# SCH_NFC-card-Michael_2024-10-10.net
KiCad netlist of a schematic drawn in EasyEDA
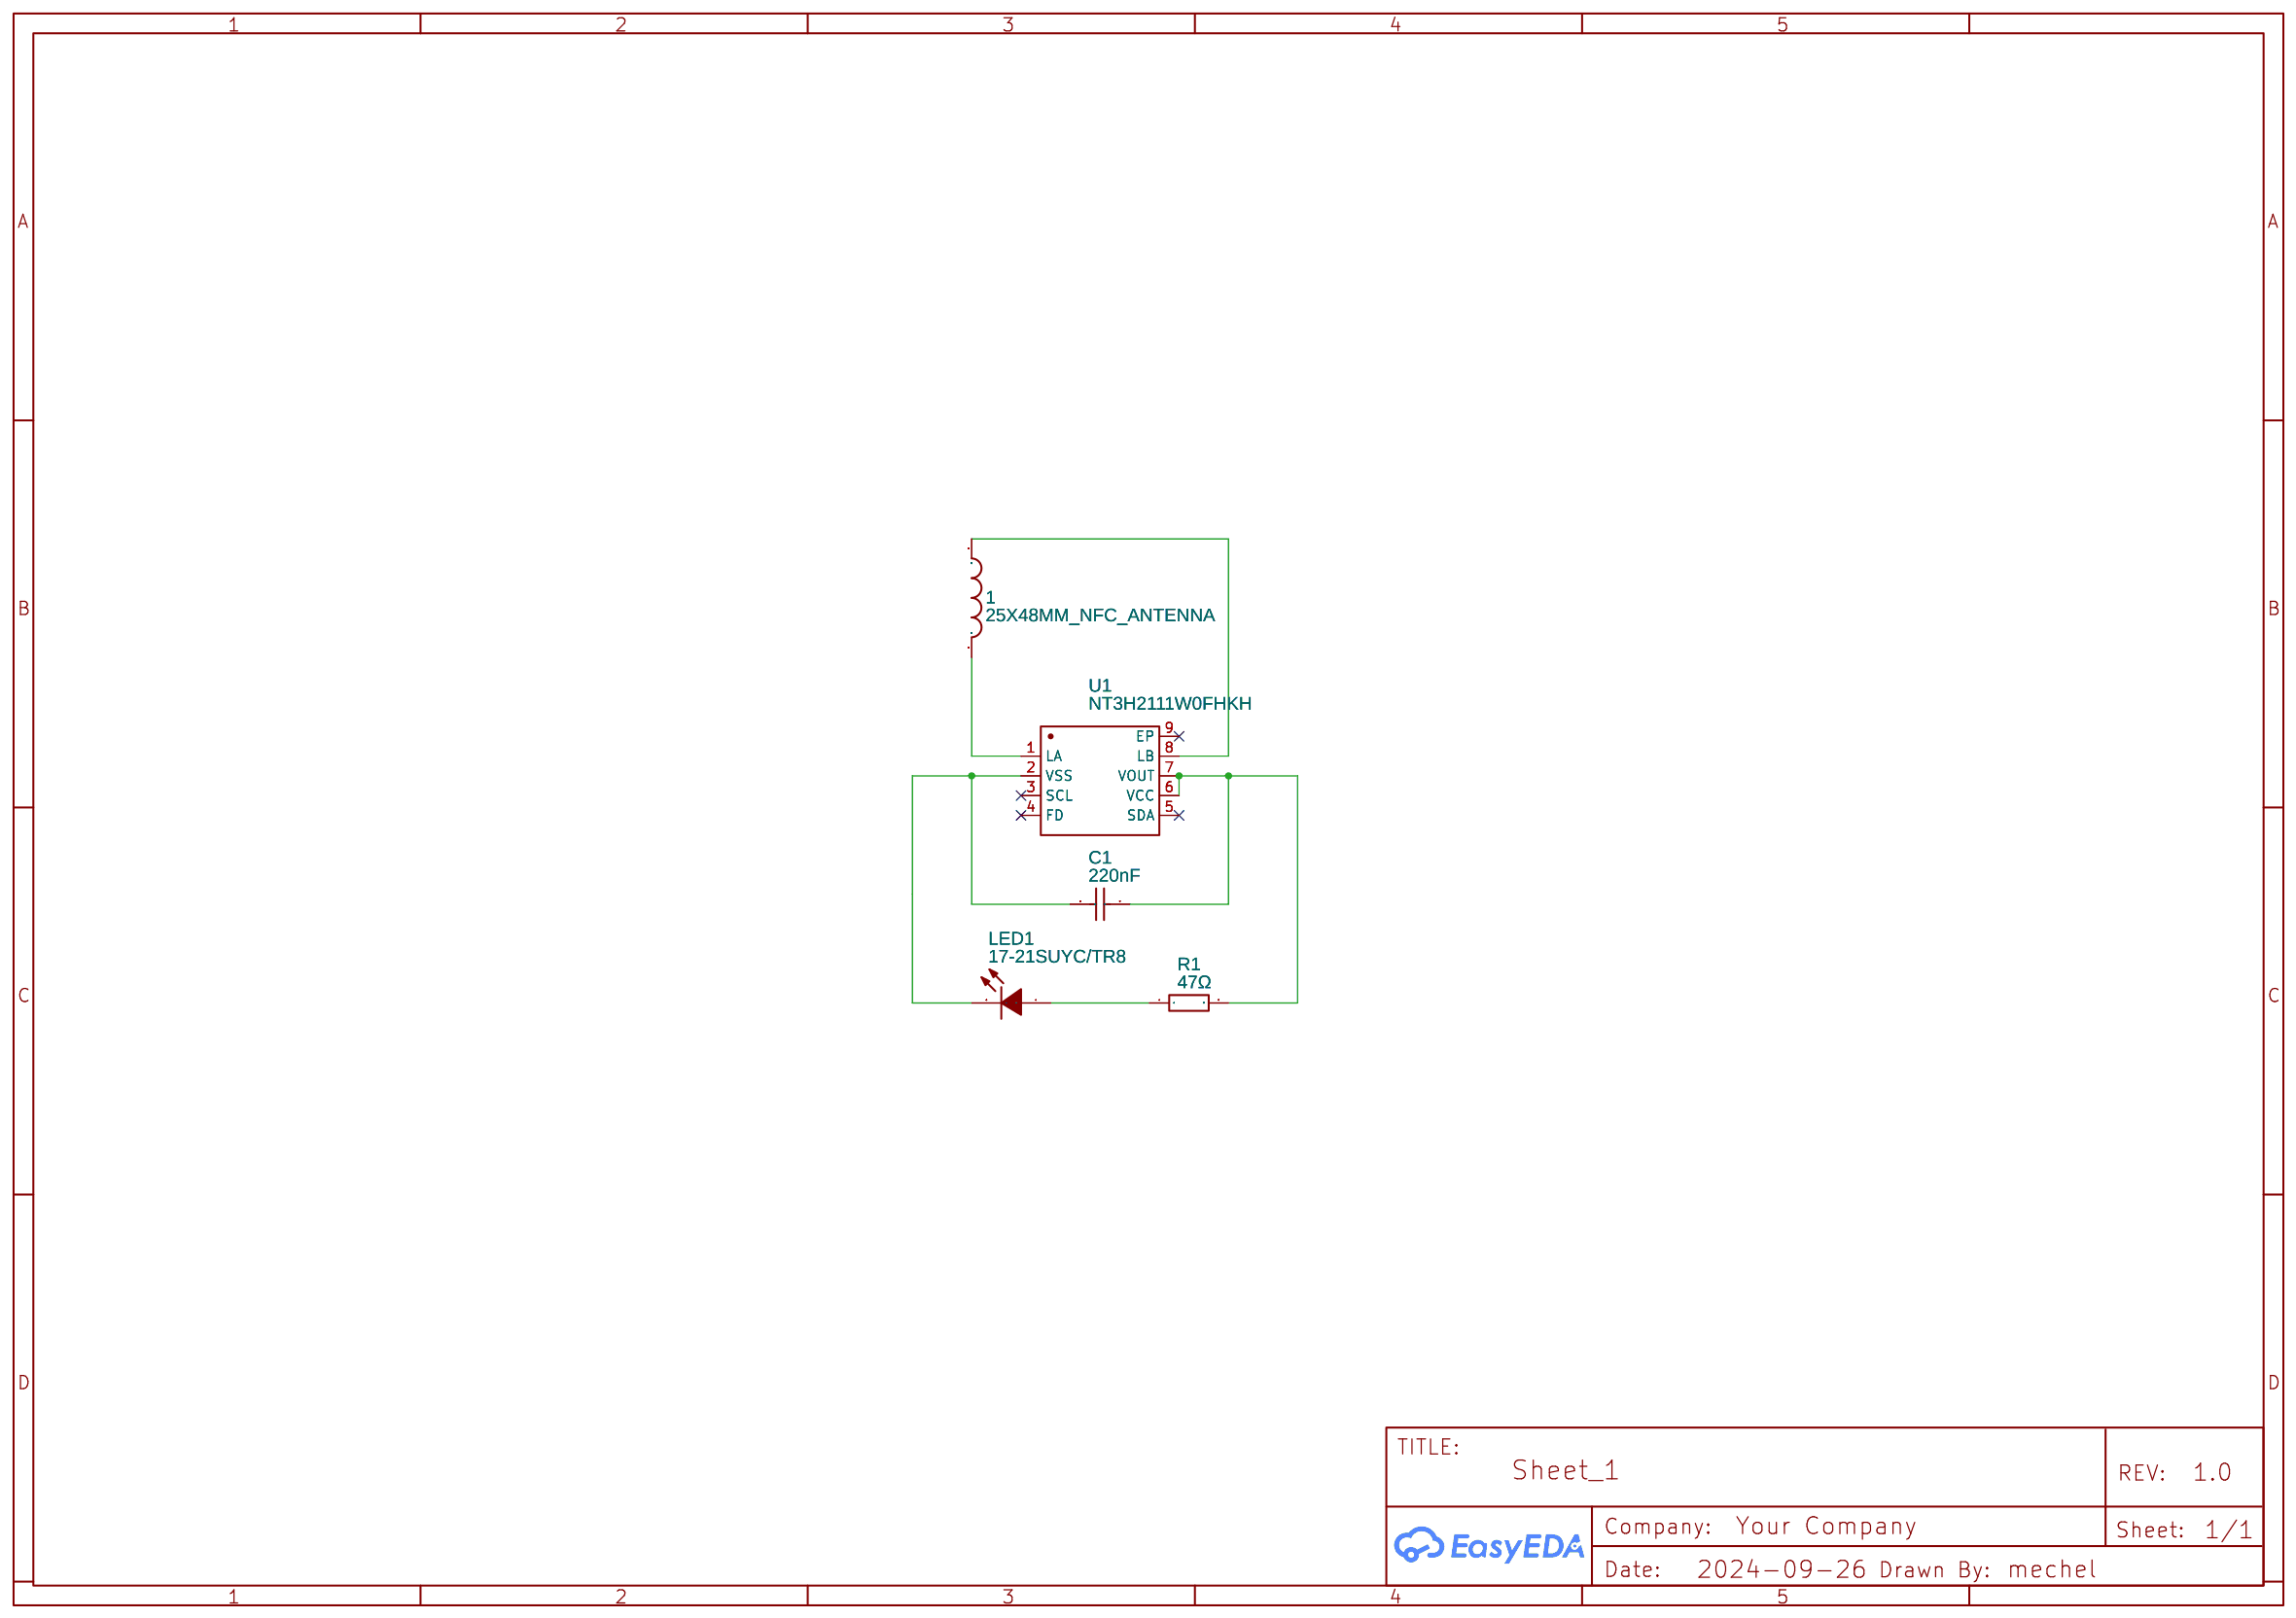
[diagram p0: schematic sheet]

(export (version "E")
  (design (tool "Eeschema 10.0.6"))
  (components
    (comp (ref "1") (value "25X48MM_NFC_ANTENNA") (libsource (lib "") (part "25X48MM_NFC_ANTENNA")))
    (comp (ref "C1")
      (value "220nF")
      (fields
        (field (name "Manufacturer Part") "CL10B224KA8NNNC")
        (field (name "Manufacturer") "SAMSUNG(三星)")
      )
      (libsource (lib "") (part "CL10B224KA8NNNC"))
    )
    (comp (ref "LED1")
      (value "17-21SUYC/TR8")
      (fields (field (name "Manufacturer Part") "KT-0805黄灯") (field (name "Manufacturer") "KENTO"))
      (libsource (lib "") (part "17-21SUYC/TR8"))
    )
    (comp (ref "R1")
      (value "47Ω")
      (fields
        (field (name "Manufacturer Part") "0603WAF470JT5E")
        (field (name "Manufacturer") "UNI-ROYAL(厚声)")
      )
      (libsource (lib "") (part "0603WAF470JT5E"))
    )
    (comp (ref "U1")
      (value "NT3H2111W0FHKH")
      (fields (field (name "Manufacturer") "NXP(恩智浦)"))
      (libsource (lib "") (part "NT3H2111W0FHKH"))
    )
  )
  (nets
    (net (code "1") (name "Net-(LED1-+)") (class "Default")
      (node (ref "LED1") (pin "1") (pinfunction "+_1") (pintype "unspecified"))
      (node (ref "R1") (pin "1") (pinfunction "1_1") (pintype "input"))
    )
    (net (code "2") (name "Net-(LED1--)") (class "Default")
      (node (ref "C1") (pin "1") (pinfunction "1_1") (pintype "input"))
      (node (ref "LED1") (pin "2") (pinfunction "-_2") (pintype "unspecified"))
      (node (ref "U1") (pin "2") (pinfunction "VSS_2") (pintype "unspecified"))
    )
    (net (code "3") (name "Net-(U1-LA)") (class "Default")
      (node (ref "1") (pin "P$2") (pinfunction "P$2_P$2") (pintype "bidirectional"))
      (node (ref "U1") (pin "1") (pinfunction "LA_1") (pintype "unspecified"))
    )
    (net (code "4") (name "Net-(U1-LB)") (class "Default")
      (node (ref "1") (pin "P$1") (pinfunction "P$1_P$1") (pintype "bidirectional"))
      (node (ref "U1") (pin "8") (pinfunction "LB_8") (pintype "unspecified"))
    )
    (net (code "5") (name "Net-(U1-VCC)") (class "Default")
      (node (ref "C1") (pin "2") (pinfunction "2_2") (pintype "input"))
      (node (ref "R1") (pin "2") (pinfunction "2_2") (pintype "input"))
      (node (ref "U1") (pin "6") (pinfunction "VCC_6") (pintype "unspecified"))
      (node (ref "U1") (pin "7") (pinfunction "VOUT_7") (pintype "unspecified"))
    )
    (net (code "6") (name "unconnected-(U1-EP-Pad9)") (class "Default")
      (node (ref "U1") (pin "9") (pinfunction "EP_9") (pintype "unspecified+no_connect"))
    )
    (net (code "7") (name "unconnected-(U1-FD-Pad4)") (class "Default")
      (node (ref "U1") (pin "4") (pinfunction "FD_4") (pintype "unspecified+no_connect"))
    )
    (net (code "8") (name "unconnected-(U1-SCL-Pad3)") (class "Default")
      (node (ref "U1") (pin "3") (pinfunction "SCL_3") (pintype "unspecified+no_connect"))
    )
    (net (code "9") (name "unconnected-(U1-SDA-Pad5)") (class "Default")
      (node (ref "U1") (pin "5") (pinfunction "SDA_5") (pintype "unspecified+no_connect"))
    )
  )
)
